# ArtNet_DMX_Controller.net
KiCad netlist of a schematic drawn in EAGLE
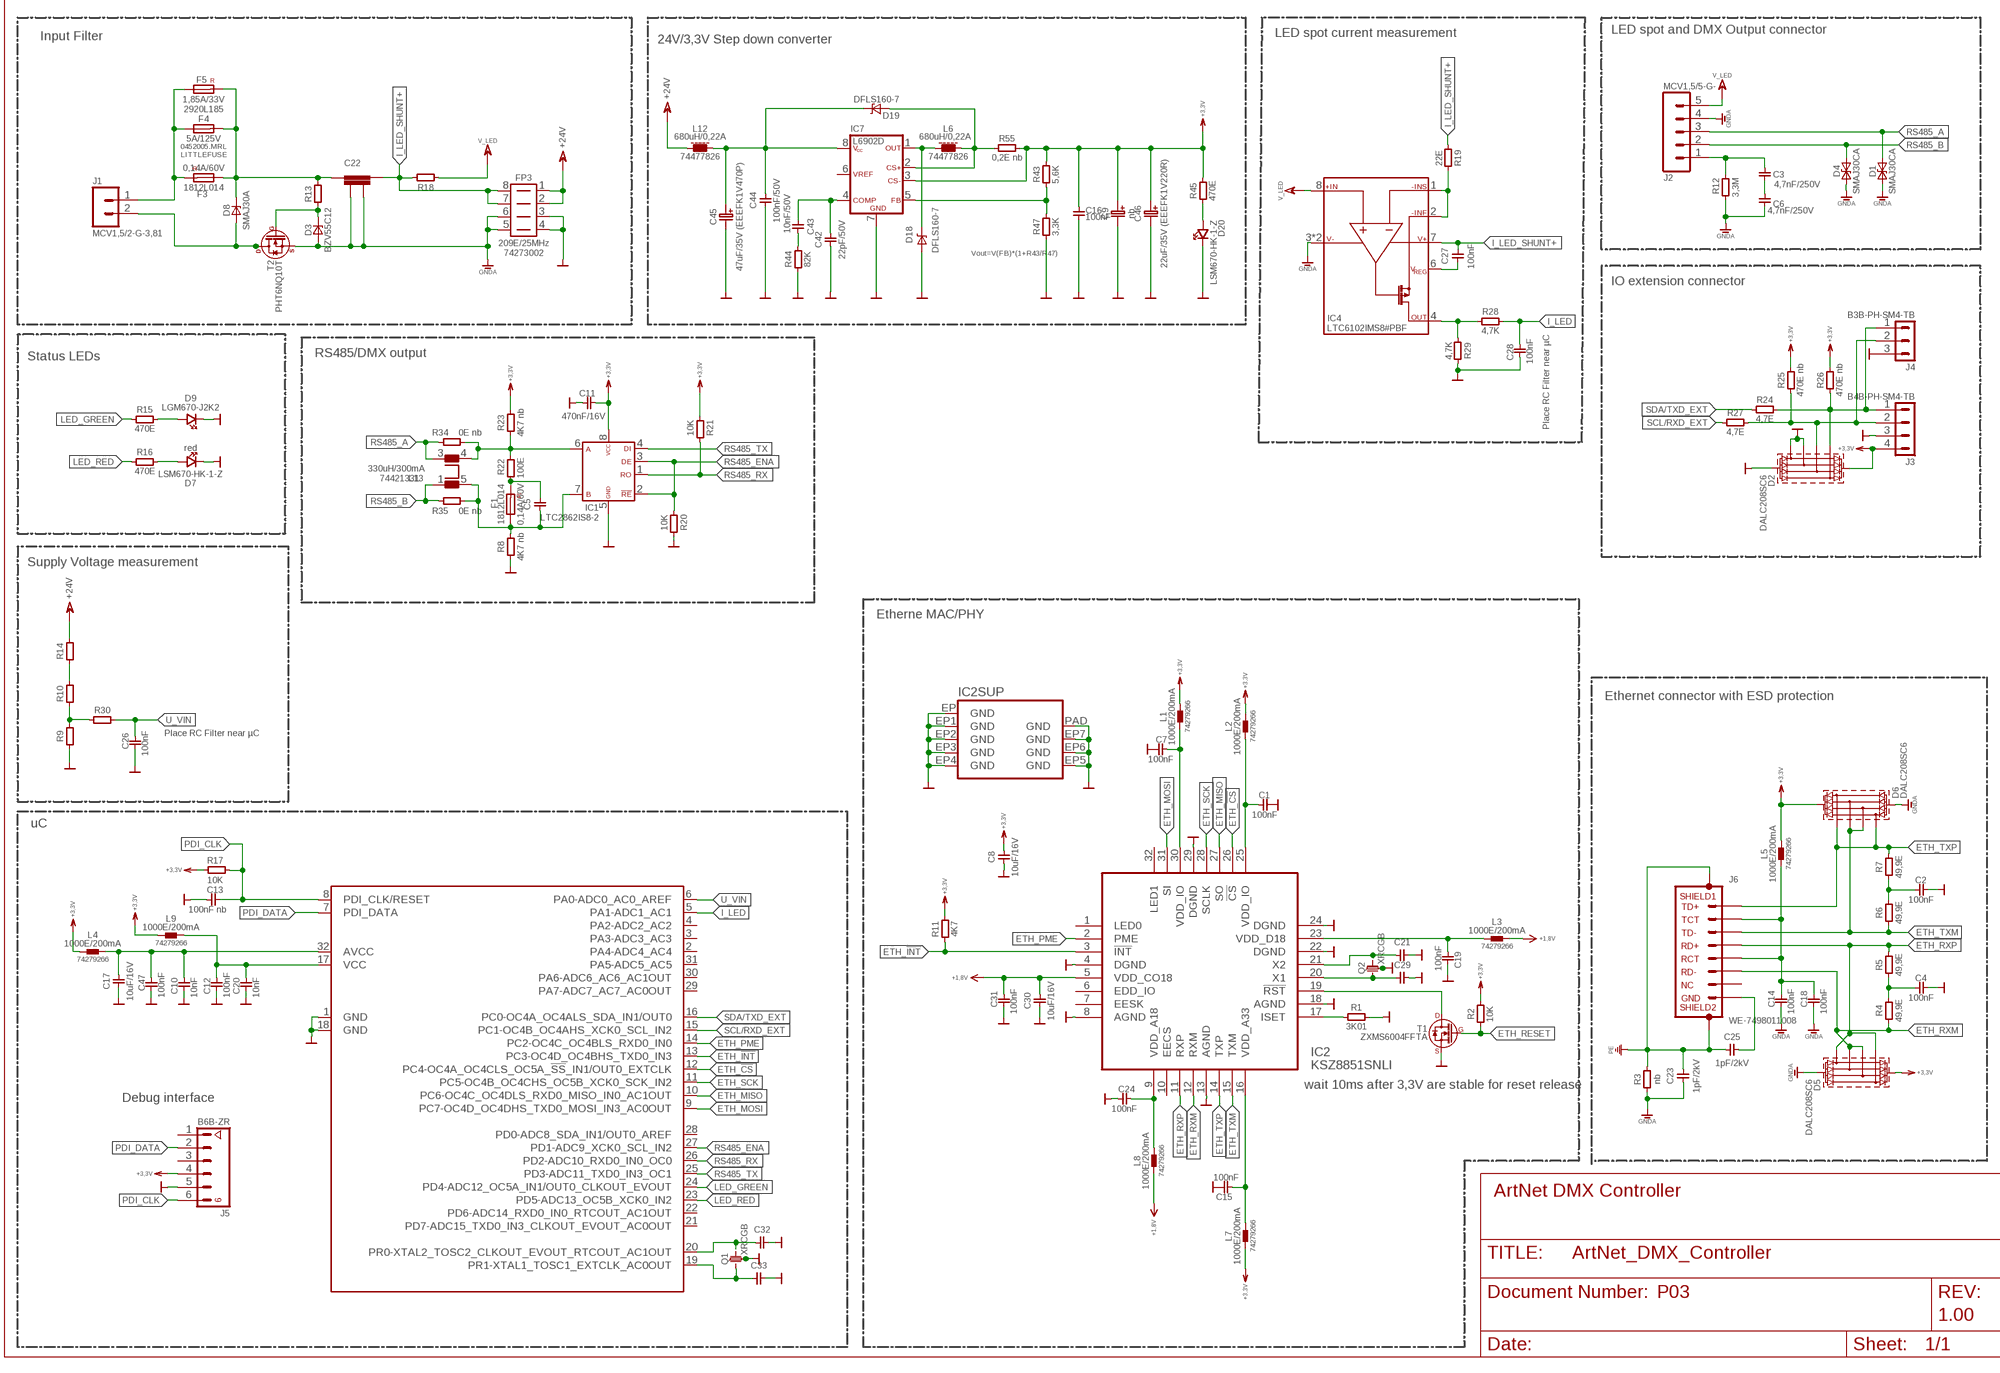
[diagram p0: schematic, sheet 1, part 1 of 2]
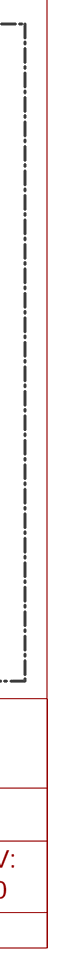
[diagram p1: schematic, sheet 1, part 2 of 2]

(export (version "E")
  (design (tool "Eeschema 10.0.6"))
  (components
    (comp (ref "C1")
      (value "100nF")
      (footprint "eagle-import:0603")
      (libsource (lib "eagle-import") (part "C-0603"))
    )
    (comp (ref "C2")
      (value "100nF")
      (footprint "eagle-import:0603")
      (libsource (lib "eagle-import") (part "C-0603"))
    )
    (comp (ref "C3")
      (value "4,7nF/250V")
      (footprint "eagle-import:2220")
      (libsource (lib "eagle-import") (part "C-2220"))
    )
    (comp (ref "C4")
      (value "100nF")
      (footprint "eagle-import:0603")
      (libsource (lib "eagle-import") (part "C-0603"))
    )
    (comp (ref "C5")
      (value "C-0805")
      (footprint "eagle-import:0805")
      (libsource (lib "eagle-import") (part "C-0805"))
    )
    (comp (ref "C6")
      (value "4,7nF/250V")
      (footprint "eagle-import:2220")
      (libsource (lib "eagle-import") (part "C-2220"))
    )
    (comp (ref "C7")
      (value "100nF")
      (footprint "eagle-import:0603")
      (libsource (lib "eagle-import") (part "C-0603"))
    )
    (comp (ref "C8")
      (value "10uF/16V")
      (footprint "eagle-import:0805")
      (libsource (lib "eagle-import") (part "C-0805"))
    )
    (comp (ref "C9")
      (value "nb")
      (footprint "eagle-import:6032")
      (libsource (lib "eagle-import") (part "TANTAL-6032"))
    )
    (comp (ref "C10")
      (value "10nF")
      (footprint "eagle-import:0603")
      (libsource (lib "eagle-import") (part "C-0603"))
    )
    (comp (ref "C11")
      (value "470nF/16V")
      (footprint "eagle-import:0603")
      (libsource (lib "eagle-import") (part "C-0603"))
    )
    (comp (ref "C12")
      (value "100nF")
      (footprint "eagle-import:0603")
      (libsource (lib "eagle-import") (part "C-0603"))
    )
    (comp (ref "C13")
      (value "100nF nb")
      (footprint "eagle-import:0603")
      (libsource (lib "eagle-import") (part "C-0603"))
    )
    (comp (ref "C14")
      (value "100nF")
      (footprint "eagle-import:0603")
      (libsource (lib "eagle-import") (part "C-0603"))
    )
    (comp (ref "C15")
      (value "100nF")
      (footprint "eagle-import:0603")
      (libsource (lib "eagle-import") (part "C-0603"))
    )
    (comp (ref "C16")
      (value "100nF")
      (footprint "eagle-import:0603")
      (libsource (lib "eagle-import") (part "C-0603"))
    )
    (comp (ref "C17")
      (value "10uF/16V")
      (footprint "eagle-import:0805")
      (libsource (lib "eagle-import") (part "C-0805"))
    )
    (comp (ref "C18")
      (value "100nF")
      (footprint "eagle-import:0603")
      (libsource (lib "eagle-import") (part "C-0603"))
    )
    (comp (ref "C19")
      (value "100nF")
      (footprint "eagle-import:0603")
      (libsource (lib "eagle-import") (part "C-0603"))
    )
    (comp (ref "C20")
      (value "10nF")
      (footprint "eagle-import:0603")
      (libsource (lib "eagle-import") (part "C-0603"))
    )
    (comp (ref "C21")
      (value "C-0603")
      (footprint "eagle-import:0603")
      (libsource (lib "eagle-import") (part "C-0603"))
    )
    (comp (ref "C22")
      (value "NFM55P")
      (footprint "eagle-import:NFM55P")
      (libsource (lib "eagle-import") (part "NFM?55P"))
    )
    (comp (ref "C23")
      (value "1pF/2kV")
      (footprint "eagle-import:1206")
      (libsource (lib "eagle-import") (part "C-1206"))
    )
    (comp (ref "C24")
      (value "100nF")
      (footprint "eagle-import:0603")
      (libsource (lib "eagle-import") (part "C-0603"))
    )
    (comp (ref "C25")
      (value "1pF/2kV")
      (footprint "eagle-import:1206")
      (libsource (lib "eagle-import") (part "C-1206"))
    )
    (comp (ref "C26")
      (value "100nF")
      (footprint "eagle-import:0603")
      (libsource (lib "eagle-import") (part "C-0603"))
    )
    (comp (ref "C27")
      (value "100nF")
      (footprint "eagle-import:0805")
      (libsource (lib "eagle-import") (part "C-0805"))
    )
    (comp (ref "C28")
      (value "100nF")
      (footprint "eagle-import:0603")
      (libsource (lib "eagle-import") (part "C-0603"))
    )
    (comp (ref "C29")
      (value "C-0603")
      (footprint "eagle-import:0603")
      (libsource (lib "eagle-import") (part "C-0603"))
    )
    (comp (ref "C30")
      (value "10uF/16V")
      (footprint "eagle-import:0805")
      (libsource (lib "eagle-import") (part "C-0805"))
    )
    (comp (ref "C31")
      (value "100nF")
      (footprint "eagle-import:0603")
      (libsource (lib "eagle-import") (part "C-0603"))
    )
    (comp (ref "C32")
      (value "C-0603")
      (footprint "eagle-import:0603")
      (libsource (lib "eagle-import") (part "C-0603"))
    )
    (comp (ref "C33")
      (value "C-0603")
      (footprint "eagle-import:0603")
      (libsource (lib "eagle-import") (part "C-0603"))
    )
    (comp (ref "C42")
      (value "22pF/50V")
      (footprint "eagle-import:0603")
      (libsource (lib "eagle-import") (part "C-0603"))
    )
    (comp (ref "C43")
      (value "10nF/50V")
      (footprint "eagle-import:0603")
      (libsource (lib "eagle-import") (part "C-0603"))
    )
    (comp (ref "C44")
      (value "100nF/50V")
      (footprint "eagle-import:0805")
      (libsource (lib "eagle-import") (part "C-0805"))
    )
    (comp (ref "C45")
      (value "47uF/35V (EEEFK1V470P)")
      (footprint "eagle-import:PANASONIC-SIZE-CODE-D")
      (libsource (lib "eagle-import") (part "ELKO-PANSIZE-D"))
    )
    (comp (ref "C46")
      (value "22uF/35V (EEEFK1V220R)")
      (footprint "eagle-import:PANASONIC-SIZE-CODE-D")
      (libsource (lib "eagle-import") (part "ELKO-PANSIZE-D"))
    )
    (comp (ref "C47")
      (value "100nF")
      (footprint "eagle-import:0603")
      (libsource (lib "eagle-import") (part "C-0603"))
    )
    (comp (ref "D1")
      (value "SMAJ30CA")
      (footprint "eagle-import:DO-214AC")
      (libsource (lib "eagle-import") (part "SMAJCA30"))
    )
    (comp (ref "D2")
      (value "DALC208SC6")
      (footprint "eagle-import:SOT23-6L")
      (libsource (lib "eagle-import") (part "DALC208SC6"))
    )
    (comp (ref "D3")
      (value "BZV55C12")
      (footprint "eagle-import:SOD80C")
      (libsource (lib "eagle-import") (part "BZ?55CV12"))
    )
    (comp (ref "D4")
      (value "SMAJ30CA")
      (footprint "eagle-import:DO-214AC")
      (libsource (lib "eagle-import") (part "SMAJCA30"))
    )
    (comp (ref "D5")
      (value "DALC208SC6")
      (footprint "eagle-import:SOT23-6L")
      (libsource (lib "eagle-import") (part "DALC208SC6"))
    )
    (comp (ref "D6")
      (value "DALC208SC6")
      (footprint "eagle-import:SOT23-6L")
      (libsource (lib "eagle-import") (part "DALC208SC6"))
    )
    (comp (ref "D7")
      (value "LSM670-HK-1-Z")
      (footprint "eagle-import:M670")
      (fields (field (name "COLOR") "red"))
      (libsource (lib "eagle-import") (part "L?M670S-HK-1-Z"))
    )
    (comp (ref "D8")
      (value "SMAJ30A")
      (footprint "eagle-import:DO-214AC")
      (libsource (lib "eagle-import") (part "SMAJA30"))
    )
    (comp (ref "D9")
      (value "LGM670-J2K2")
      (footprint "eagle-import:M670")
      (libsource (lib "eagle-import") (part "L?M670G-J2K2"))
    )
    (comp (ref "D18")
      (value "DFLS160-7")
      (footprint "eagle-import:POWERDI123")
      (libsource (lib "eagle-import") (part "DFLS160-7"))
    )
    (comp (ref "D19")
      (value "DFLS160-7")
      (footprint "eagle-import:POWERDI123")
      (libsource (lib "eagle-import") (part "DFLS160-7"))
    )
    (comp (ref "D20")
      (value "LSM670-HK-1-Z")
      (footprint "eagle-import:M670")
      (libsource (lib "eagle-import") (part "L?M670S-HK-1-Z"))
    )
    (comp (ref "F1")
      (value "0,14A/60V")
      (footprint "eagle-import:1812L")
      (fields (field (name "MPN") "1812L014"))
      (libsource (lib "eagle-import") (part "1812L014"))
    )
    (comp (ref "F3")
      (value "0,14A/60V")
      (footprint "eagle-import:1812L")
      (fields (field (name "MPN") "1812L014"))
      (libsource (lib "eagle-import") (part "1812L014"))
    )
    (comp (ref "F4")
      (value "5A/125V")
      (footprint "eagle-import:6.1X2.69MM")
      (fields (field (name "MF") "LITTLEFUSE") (field (name "MPN") "0452005.MRL"))
      (libsource (lib "eagle-import") (part "0452MRL005."))
    )
    (comp (ref "F5")
      (value "1,85A/33V")
      (footprint "eagle-import:2920L")
      (fields (field (name "MPN") "2920L185"))
      (libsource (lib "eagle-import") (part "2920L185"))
    )
    (comp (ref "FP3")
      (value "209E/25MHz")
      (footprint "eagle-import:WE-MLS-10,88MMX5,49MM")
      (fields (field (name "MPN") "74273002"))
      (libsource (lib "eagle-import") (part "WE-MLS-10,88MMX5,49MM-209E/25MHZ"))
    )
    (comp (ref "IC1")
      (value "LTC2862IS8-2")
      (footprint "eagle-import:SO8")
      (fields (field (name "MPN") "LTC2862IS8-2#TRPBF"))
      (libsource (lib "eagle-import") (part "LTC2862?-2S8I"))
    )
    (comp (ref "IC2")
      (value "KSZ8851SNLI")
      (footprint "eagle-import:QFN32_5X5")
      (libsource (lib "eagle-import") (part "IC_KSZ8851SNL"))
    )
    (comp (ref "IC3")
      (value "E5-TQFP")
      (footprint "eagle-import:TQFP32")
      (libsource (lib "eagle-import") (part "E5-TQFP"))
    )
    (comp (ref "IC4")
      (value "LTC6102IMS8#PBF")
      (footprint "eagle-import:MS8")
      (libsource (lib "eagle-import") (part "LTC6102?#PBFMS8I"))
    )
    (comp (ref "IC7")
      (value "L6902D")
      (footprint "eagle-import:SO8")
      (libsource (lib "eagle-import") (part "L6902D"))
    )
    (comp (ref "J1")
      (value "MCV1,5/2-G-3,81")
      (footprint "eagle-import:MCV1,5_2-G-3,81")
      (libsource (lib "eagle-import") (part "MCV1,5/2-G-3,81"))
    )
    (comp (ref "J2")
      (value "MCV1,5/5-G-")
      (footprint "eagle-import:MCV1,5_5-G-3,81_MOD")
      (libsource (lib "eagle-import") (part "MCV1,5/5-G-?"))
    )
    (comp (ref "J3")
      (value "B4B-PH-SM4-TB")
      (footprint "eagle-import:B4B-PH-SM4-TB")
      (libsource (lib "eagle-import") (part "?4B-PH-SM4-TBB"))
    )
    (comp (ref "J4")
      (value "B3B-PH-SM4-TB")
      (footprint "eagle-import:B3B-PH-SM4-TB")
      (libsource (lib "eagle-import") (part "?3B-PH-SM4-TBB"))
    )
    (comp (ref "J5")
      (value "B6B-ZR")
      (footprint "eagle-import:B6B-ZR")
      (libsource (lib "eagle-import") (part "?6B-ZRB"))
    )
    (comp (ref "J6")
      (value "WE-7498011008")
      (footprint "eagle-import:WE-749801108")
      (libsource (lib "eagle-import") (part "WE-7498011008"))
    )
    (comp (ref "L1")
      (value "1000E/200mA")
      (footprint "eagle-import:0603")
      (fields (field (name "MPN") "74279266"))
      (libsource (lib "eagle-import") (part "WE-CBF-0603-1000E/200MA"))
    )
    (comp (ref "L2")
      (value "1000E/200mA")
      (footprint "eagle-import:0603")
      (fields (field (name "MPN") "74279266"))
      (libsource (lib "eagle-import") (part "WE-CBF-0603-1000E/200MA"))
    )
    (comp (ref "L3")
      (value "1000E/200mA")
      (footprint "eagle-import:0603")
      (fields (field (name "MPN") "74279266"))
      (libsource (lib "eagle-import") (part "WE-CBF-0603-1000E/200MA"))
    )
    (comp (ref "L4")
      (value "1000E/200mA")
      (footprint "eagle-import:0603")
      (fields (field (name "MPN") "74279266"))
      (libsource (lib "eagle-import") (part "WE-CBF-0603-1000E/200MA"))
    )
    (comp (ref "L5")
      (value "1000E/200mA")
      (footprint "eagle-import:0603")
      (fields (field (name "MPN") "74279266"))
      (libsource (lib "eagle-import") (part "WE-CBF-0603-1000E/200MA"))
    )
    (comp (ref "L6")
      (value "680uH/0,22A")
      (footprint "eagle-import:73XX")
      (fields (field (name "MPN") "74477826"))
      (libsource (lib "eagle-import") (part "WE-PD-7332-680UH/0,22A"))
    )
    (comp (ref "L7")
      (value "1000E/200mA")
      (footprint "eagle-import:0603")
      (fields (field (name "MPN") "74279266"))
      (libsource (lib "eagle-import") (part "WE-CBF-0603-1000E/200MA"))
    )
    (comp (ref "L8")
      (value "1000E/200mA")
      (footprint "eagle-import:0603")
      (fields (field (name "MPN") "74279266"))
      (libsource (lib "eagle-import") (part "WE-CBF-0603-1000E/200MA"))
    )
    (comp (ref "L9")
      (value "1000E/200mA")
      (footprint "eagle-import:0603")
      (fields (field (name "MPN") "74279266"))
      (libsource (lib "eagle-import") (part "WE-CBF-0603-1000E/200MA"))
    )
    (comp (ref "L12")
      (value "680uH/0,22A")
      (footprint "eagle-import:73XX")
      (fields (field (name "MPN") "74477826"))
      (libsource (lib "eagle-import") (part "WE-PD-7332-680UH/0,22A"))
    )
    (comp (ref "L13")
      (value "330uH/300mA")
      (footprint "eagle-import:WE-SL1")
      (fields (field (name "MPN") "74421331"))
      (libsource (lib "eagle-import") (part "WE-SL1-330UH/300MA"))
    )
    (comp (ref "Q1")
      (value "XRCGB")
      (footprint "eagle-import:XRCGB")
      (libsource (lib "eagle-import") (part "XRCGB"))
    )
    (comp (ref "Q2")
      (value "XRCGB")
      (footprint "eagle-import:XRCGB")
      (libsource (lib "eagle-import") (part "XRCGB"))
    )
    (comp (ref "R1")
      (value "3K01")
      (footprint "eagle-import:0603")
      (libsource (lib "eagle-import") (part "R-0603"))
    )
    (comp (ref "R2")
      (value "10K")
      (footprint "eagle-import:0603")
      (libsource (lib "eagle-import") (part "R-0603"))
    )
    (comp (ref "R3")
      (value "nb")
      (footprint "eagle-import:1206")
      (libsource (lib "eagle-import") (part "R-1206"))
    )
    (comp (ref "R4")
      (value "49,9E")
      (footprint "eagle-import:0603")
      (libsource (lib "eagle-import") (part "R-0603"))
    )
    (comp (ref "R5")
      (value "49,9E")
      (footprint "eagle-import:0603")
      (libsource (lib "eagle-import") (part "R-0603"))
    )
    (comp (ref "R6")
      (value "49,9E")
      (footprint "eagle-import:0603")
      (libsource (lib "eagle-import") (part "R-0603"))
    )
    (comp (ref "R7")
      (value "49,9E")
      (footprint "eagle-import:0603")
      (libsource (lib "eagle-import") (part "R-0603"))
    )
    (comp (ref "R8")
      (value "4K7 nb")
      (footprint "eagle-import:0805")
      (libsource (lib "eagle-import") (part "R-0805"))
    )
    (comp (ref "R9")
      (value "R-0603")
      (footprint "eagle-import:0603")
      (libsource (lib "eagle-import") (part "R-0603"))
    )
    (comp (ref "R10")
      (value "R-0603")
      (footprint "eagle-import:0603")
      (libsource (lib "eagle-import") (part "R-0603"))
    )
    (comp (ref "R11")
      (value "4K7")
      (footprint "eagle-import:0603")
      (libsource (lib "eagle-import") (part "R-0603"))
    )
    (comp (ref "R12")
      (value "3,3M")
      (footprint "eagle-import:0207")
      (libsource (lib "eagle-import") (part "R-0207"))
    )
    (comp (ref "R13")
      (value "R-0805")
      (footprint "eagle-import:0805")
      (libsource (lib "eagle-import") (part "R-0805"))
    )
    (comp (ref "R14")
      (value "R-0603")
      (footprint "eagle-import:0603")
      (libsource (lib "eagle-import") (part "R-0603"))
    )
    (comp (ref "R15")
      (value "470E")
      (footprint "eagle-import:0603")
      (libsource (lib "eagle-import") (part "R-0603"))
    )
    (comp (ref "R16")
      (value "470E")
      (footprint "eagle-import:0603")
      (libsource (lib "eagle-import") (part "R-0603"))
    )
    (comp (ref "R17")
      (value "10K")
      (footprint "eagle-import:0603")
      (libsource (lib "eagle-import") (part "R-0603"))
    )
    (comp (ref "R18")
      (value "R-2512")
      (footprint "eagle-import:2512")
      (libsource (lib "eagle-import") (part "R-2512"))
    )
    (comp (ref "R19")
      (value "22E")
      (footprint "eagle-import:0603")
      (libsource (lib "eagle-import") (part "R-0603"))
    )
    (comp (ref "R20")
      (value "10K")
      (footprint "eagle-import:0603")
      (libsource (lib "eagle-import") (part "R-0603"))
    )
    (comp (ref "R21")
      (value "10K")
      (footprint "eagle-import:0603")
      (libsource (lib "eagle-import") (part "R-0603"))
    )
    (comp (ref "R22")
      (value "100E")
      (footprint "eagle-import:0207")
      (libsource (lib "eagle-import") (part "R-0207"))
    )
    (comp (ref "R23")
      (value "4K7 nb")
      (footprint "eagle-import:0805")
      (libsource (lib "eagle-import") (part "R-0805"))
    )
    (comp (ref "R24")
      (value "4,7E")
      (footprint "eagle-import:0603")
      (libsource (lib "eagle-import") (part "R-0603"))
    )
    (comp (ref "R25")
      (value "470E nb")
      (footprint "eagle-import:0603")
      (libsource (lib "eagle-import") (part "R-0603"))
    )
    (comp (ref "R26")
      (value "470E nb")
      (footprint "eagle-import:0603")
      (libsource (lib "eagle-import") (part "R-0603"))
    )
    (comp (ref "R27")
      (value "4,7E")
      (footprint "eagle-import:0603")
      (libsource (lib "eagle-import") (part "R-0603"))
    )
    (comp (ref "R28")
      (value "4,7K")
      (footprint "eagle-import:0603")
      (libsource (lib "eagle-import") (part "R-0603"))
    )
    (comp (ref "R29")
      (value "4,7K")
      (footprint "eagle-import:0603")
      (libsource (lib "eagle-import") (part "R-0603"))
    )
    (comp (ref "R30")
      (value "R-0603")
      (footprint "eagle-import:0603")
      (libsource (lib "eagle-import") (part "R-0603"))
    )
    (comp (ref "R34")
      (value "0E nb")
      (footprint "eagle-import:0805")
      (libsource (lib "eagle-import") (part "R-0805"))
    )
    (comp (ref "R35")
      (value "0E nb")
      (footprint "eagle-import:0805")
      (libsource (lib "eagle-import") (part "R-0805"))
    )
    (comp (ref "R43")
      (value "5,6K")
      (footprint "eagle-import:0603")
      (libsource (lib "eagle-import") (part "R-0603"))
    )
    (comp (ref "R44")
      (value "82K")
      (footprint "eagle-import:0603")
      (libsource (lib "eagle-import") (part "R-0603"))
    )
    (comp (ref "R45")
      (value "470E")
      (footprint "eagle-import:0603")
      (libsource (lib "eagle-import") (part "R-0603"))
    )
    (comp (ref "R47")
      (value "3,3K")
      (footprint "eagle-import:0603")
      (libsource (lib "eagle-import") (part "R-0603"))
    )
    (comp (ref "R55")
      (value "0,2E nb")
      (footprint "eagle-import:0805")
      (libsource (lib "eagle-import") (part "R-0805"))
    )
    (comp (ref "T1")
      (value "ZXMS6004FFTA")
      (footprint "eagle-import:SOT-23")
      (libsource (lib "eagle-import") (part "ZXMS6004?TAFF"))
    )
    (comp (ref "T2")
      (value "PHT6NQ10T")
      (footprint "eagle-import:SOT223")
      (libsource (lib "eagle-import") (part "PHT6NQ10T"))
    )
  )
  (nets
    (net (code "1") (name "+1,8V") (class "Default")
      (node (ref "C30") (pin "2") (pinfunction "2_2") (pintype "passive"))
      (node (ref "C31") (pin "2") (pinfunction "2_2") (pintype "passive"))
      (node (ref "IC2") (pin "5") (pinfunction "VDD_CO18_5") (pintype "bidirectional"))
      (node (ref "L3") (pin "2") (pinfunction "2_2") (pintype "passive"))
      (node (ref "L8") (pin "1") (pinfunction "1_1") (pintype "passive"))
    )
    (net (code "2") (name "+3,3V") (class "Default")
      (node (ref "C11") (pin "2") (pinfunction "2_2") (pintype "passive"))
      (node (ref "C16") (pin "2") (pinfunction "2_2") (pintype "passive"))
      (node (ref "C46") (pin "+") (pinfunction "+_+") (pintype "passive"))
      (node (ref "C8") (pin "1") (pinfunction "1_1") (pintype "passive"))
      (node (ref "C9") (pin "PLUS") (pinfunction "+_PLUS") (pintype "passive"))
      (node (ref "D2") (pin "2") (pinfunction "REF2_2") (pintype "passive"))
      (node (ref "D5") (pin "2") (pinfunction "REF2_2") (pintype "passive"))
      (node (ref "D6") (pin "2") (pinfunction "REF2_2") (pintype "passive"))
      (node (ref "IC1") (pin "8") (pinfunction "VCC_8") (pintype "power_in"))
      (node (ref "IC7") (pin "3") (pinfunction "CS-_3") (pintype "input"))
      (node (ref "J3") (pin "4") (pinfunction "4_4") (pintype "passive"))
      (node (ref "J5") (pin "4") (pinfunction "4_4") (pintype "passive"))
      (node (ref "L1") (pin "2") (pinfunction "2_2") (pintype "passive"))
      (node (ref "L2") (pin "2") (pinfunction "2_2") (pintype "passive"))
      (node (ref "L4") (pin "1") (pinfunction "1_1") (pintype "passive"))
      (node (ref "L5") (pin "2") (pinfunction "2_2") (pintype "passive"))
      (node (ref "L7") (pin "1") (pinfunction "1_1") (pintype "passive"))
      (node (ref "L9") (pin "1") (pinfunction "1_1") (pintype "passive"))
      (node (ref "R11") (pin "2") (pinfunction "2_2") (pintype "passive"))
      (node (ref "R17") (pin "2") (pinfunction "2_2") (pintype "passive"))
      (node (ref "R2") (pin "2") (pinfunction "2_2") (pintype "passive"))
      (node (ref "R21") (pin "2") (pinfunction "2_2") (pintype "passive"))
      (node (ref "R23") (pin "2") (pinfunction "2_2") (pintype "passive"))
      (node (ref "R25") (pin "2") (pinfunction "2_2") (pintype "passive"))
      (node (ref "R26") (pin "2") (pinfunction "2_2") (pintype "passive"))
      (node (ref "R43") (pin "2") (pinfunction "2_2") (pintype "passive"))
      (node (ref "R45") (pin "2") (pinfunction "2_2") (pintype "passive"))
      (node (ref "R55") (pin "2") (pinfunction "2_2") (pintype "passive"))
    )
    (net (code "3") (name "+24V") (class "Default")
      (node (ref "FP3") (pin "1") (pinfunction "1_1") (pintype "passive"))
      (node (ref "FP3") (pin "2") (pinfunction "2_2") (pintype "passive"))
      (node (ref "L12") (pin "1") (pinfunction "1_1") (pintype "passive"))
      (node (ref "R14") (pin "2") (pinfunction "2_2") (pintype "passive"))
    )
    (net (code "4") (name "/ETH_~{CS}") (class "Default")
      (node (ref "IC2") (pin "26") (pinfunction "~{CS}_26") (pintype "bidirectional"))
      (node (ref "IC3") (pin "12") (pinfunction "PC4-OC4A_OC4CLS_OC5A_~{SS}_IN1/OUT0_EXTCLK_12") (pintype "bidirectional"))
    )
    (net (code "5") (name "/ETH_~{INT}") (class "Default")
      (node (ref "IC2") (pin "3") (pinfunction "~{INT}_3") (pintype "bidirectional"))
      (node (ref "IC3") (pin "13") (pinfunction "PC3-OC4D_OC4BHS_TXD0_IN3_13") (pintype "bidirectional"))
      (node (ref "R11") (pin "1") (pinfunction "1_1") (pintype "passive"))
    )
    (net (code "6") (name "ETH_MISO") (class "Default")
      (node (ref "IC2") (pin "27") (pinfunction "SO_27") (pintype "bidirectional"))
      (node (ref "IC3") (pin "10") (pinfunction "PC6-OC4C_OC4DLS_RXD0_MISO_IN0_AC1OUT_10") (pintype "bidirectional"))
    )
    (net (code "7") (name "ETH_MOSI") (class "Default")
      (node (ref "IC2") (pin "31") (pinfunction "SI_31") (pintype "bidirectional"))
      (node (ref "IC3") (pin "9") (pinfunction "PC7-OC4D_OC4DHS_TXD0_MOSI_IN3_AC0OUT_9") (pintype "bidirectional"))
    )
    (net (code "8") (name "ETH_PME") (class "Default")
      (node (ref "IC2") (pin "2") (pinfunction "PME_2") (pintype "bidirectional"))
      (node (ref "IC3") (pin "14") (pinfunction "PC2-OC4C_OC4BLS_RXD0_IN0_14") (pintype "bidirectional"))
    )
    (net (code "9") (name "ETH_RESET") (class "Default")
      (node (ref "R2") (pin "1") (pinfunction "1_1") (pintype "passive"))
      (node (ref "T1") (pin "1") (pinfunction "G_1") (pintype "passive"))
    )
    (net (code "10") (name "ETH_RXM") (class "Default")
      (node (ref "D5") (pin "3") (pinfunction "I/O2_3") (pintype "passive"))
      (node (ref "D5") (pin "4") (pinfunction "I/O3_4") (pintype "passive"))
      (node (ref "IC2") (pin "12") (pinfunction "RXM_12") (pintype "bidirectional"))
      (node (ref "J6") (pin "P$6") (pinfunction "RD-_P$6") (pintype "passive"))
      (node (ref "R4") (pin "1") (pinfunction "1_1") (pintype "passive"))
    )
    (net (code "11") (name "ETH_RXP") (class "Default")
      (node (ref "D5") (pin "1") (pinfunction "I/O1_1") (pintype "passive"))
      (node (ref "D5") (pin "6") (pinfunction "I/O4_6") (pintype "passive"))
      (node (ref "IC2") (pin "11") (pinfunction "RXP_11") (pintype "bidirectional"))
      (node (ref "J6") (pin "P$3") (pinfunction "RD+_P$3") (pintype "passive"))
      (node (ref "R5") (pin "2") (pinfunction "2_2") (pintype "passive"))
    )
    (net (code "12") (name "ETH_SCK") (class "Default")
      (node (ref "IC2") (pin "28") (pinfunction "SCLK_28") (pintype "bidirectional"))
      (node (ref "IC3") (pin "11") (pinfunction "PC5-OC4B_OC4CHS_OC5B_XCK0_SCK_IN2_11") (pintype "bidirectional"))
    )
    (net (code "13") (name "ETH_TXM") (class "Default")
      (node (ref "D6") (pin "3") (pinfunction "I/O2_3") (pintype "passive"))
      (node (ref "D6") (pin "4") (pinfunction "I/O3_4") (pintype "passive"))
      (node (ref "IC2") (pin "15") (pinfunction "TXM_15") (pintype "bidirectional"))
      (node (ref "J6") (pin "P$2") (pinfunction "TD-_P$2") (pintype "passive"))
      (node (ref "R6") (pin "1") (pinfunction "1_1") (pintype "passive"))
    )
    (net (code "14") (name "ETH_TXP") (class "Default")
      (node (ref "D6") (pin "1") (pinfunction "I/O1_1") (pintype "passive"))
      (node (ref "D6") (pin "6") (pinfunction "I/O4_6") (pintype "passive"))
      (node (ref "IC2") (pin "14") (pinfunction "TXP_14") (pintype "bidirectional"))
      (node (ref "J6") (pin "P$1") (pinfunction "TD+_P$1") (pintype "passive"))
      (node (ref "R7") (pin "2") (pinfunction "2_2") (pintype "passive"))
    )
    (net (code "15") (name "GND") (class "Default")
      (node (ref "C1") (pin "2") (pinfunction "2_2") (pintype "passive"))
      (node (ref "C10") (pin "1") (pinfunction "1_1") (pintype "passive"))
      (node (ref "C11") (pin "1") (pinfunction "1_1") (pintype "passive"))
      (node (ref "C12") (pin "1") (pinfunction "1_1") (pintype "passive"))
      (node (ref "C13") (pin "2") (pinfunction "2_2") (pintype "passive"))
      (node (ref "C15") (pin "2") (pinfunction "2_2") (pintype "passive"))
      (node (ref "C16") (pin "1") (pinfunction "1_1") (pintype "passive"))
      (node (ref "C17") (pin "1") (pinfunction "1_1") (pintype "passive"))
      (node (ref "C19") (pin "2") (pinfunction "2_2") (pintype "passive"))
      (node (ref "C2") (pin "2") (pinfunction "2_2") (pintype "passive"))
      (node (ref "C20") (pin "1") (pinfunction "1_1") (pintype "passive"))
      (node (ref "C21") (pin "2") (pinfunction "2_2") (pintype "passive"))
      (node (ref "C24") (pin "1") (pinfunction "1_1") (pintype "passive"))
      (node (ref "C26") (pin "1") (pinfunction "1_1") (pintype "passive"))
      (node (ref "C28") (pin "1") (pinfunction "1_1") (pintype "passive"))
      (node (ref "C29") (pin "2") (pinfunction "2_2") (pintype "passive"))
      (node (ref "C30") (pin "1") (pinfunction "1_1") (pintype "passive"))
      (node (ref "C31") (pin "1") (pinfunction "1_1") (pintype "passive"))
      (node (ref "C32") (pin "2") (pinfunction "2_2") (pintype "passive"))
      (node (ref "C33") (pin "2") (pinfunction "2_2") (pintype "passive"))
      (node (ref "C4") (pin "2") (pinfunction "2_2") (pintype "passive"))
      (node (ref "C42") (pin "1") (pinfunction "1_1") (pintype "passive"))
      (node (ref "C44") (pin "1") (pinfunction "1_1") (pintype "passive"))
      (node (ref "C45") (pin "-") (pinfunction "-_-") (pintype "passive"))
      (node (ref "C46") (pin "-") (pinfunction "-_-") (pintype "passive"))
      (node (ref "C47") (pin "1") (pinfunction "1_1") (pintype "passive"))
      (node (ref "C7") (pin "2") (pinfunction "2_2") (pintype "passive"))
      (node (ref "C8") (pin "2") (pinfunction "2_2") (pintype "passive"))
      (node (ref "C9") (pin "MINUS") (pinfunction "-_MINUS") (pintype "passive"))
      (node (ref "D18") (pin "A") (pinfunction "A_A") (pintype "passive"))
      (node (ref "D2") (pin "1") (pinfunction "I/O1_1") (pintype "passive"))
      (node (ref "D2") (pin "3") (pinfunction "I/O2_3") (pintype "passive"))
      (node (ref "D2") (pin "5") (pinfunction "REF1_5") (pintype "passive"))
      (node (ref "D20") (pin "K") (pinfunction "K_K") (pintype "passive"))
      (node (ref "D7") (pin "K") (pinfunction "K_K") (pintype "passive"))
      (node (ref "D9") (pin "K") (pinfunction "K_K") (pintype "passive"))
      (node (ref "FP3") (pin "3") (pinfunction "3_3") (pintype "passive"))
      (node (ref "FP3") (pin "4") (pinfunction "4_4") (pintype "passive"))
      (node (ref "IC1") (pin "5") (pinfunction "GND_5") (pintype "power_in"))
      (node (ref "IC2") (pin "13") (pinfunction "AGND_13") (pintype "bidirectional"))
      (node (ref "IC2") (pin "18") (pinfunction "AGND_18") (pintype "power_in"))
      (node (ref "IC2") (pin "22") (pinfunction "DGND_22") (pintype "bidirectional"))
      (node (ref "IC2") (pin "24") (pinfunction "DGND_24") (pintype "bidirectional"))
      (node (ref "IC2") (pin "29") (pinfunction "DGND_29") (pintype "bidirectional"))
      (node (ref "IC2") (pin "4") (pinfunction "DGND_4") (pintype "power_in"))
      (node (ref "IC2") (pin "8") (pinfunction "AGND_8") (pintype "bidirectional"))
      (node (ref "IC2") (pin "EP") (pinfunction "GND_EP") (pintype "power_in"))
      (node (ref "IC2") (pin "EP1") (pinfunction "GND_EP1") (pintype "power_in"))
      (node (ref "IC2") (pin "EP2") (pinfunction "GND_EP2") (pintype "power_in"))
      (node (ref "IC2") (pin "EP3") (pinfunction "GND_EP3") (pintype "power_in"))
      (node (ref "IC2") (pin "EP4") (pinfunction "GND_EP4") (pintype "power_in"))
      (node (ref "IC2") (pin "EP5") (pinfunction "GND_EP5") (pintype "power_in"))
      (node (ref "IC2") (pin "EP6") (pinfunction "GND_EP6") (pintype "power_in"))
      (node (ref "IC2") (pin "EP7") (pinfunction "GND_EP7") (pintype "power_in"))
      (node (ref "IC2") (pin "PAD") (pinfunction "GND_PAD") (pintype "power_in"))
      (node (ref "IC3") (pin "1") (pinfunction "GND_1") (pintype "power_in"))
      (node (ref "IC3") (pin "18") (pinfunction "GND_18") (pintype "power_in"))
      (node (ref "IC7") (pin "7") (pinfunction "GND_7") (pintype "power_in"))
      (node (ref "J3") (pin "3") (pinfunction "3_3") (pintype "passive"))
      (node (ref "J4") (pin "3") (pinfunction "3_3") (pintype "passive"))
      (node (ref "J5") (pin "5") (pinfunction "5_5") (pintype "passive"))
      (node (ref "Q1") (pin "3") (pinfunction "P$3_3") (pintype "bidirectional"))
      (node (ref "Q1") (pin "4") (pinfunction "P$4_4") (pintype "bidirectional"))
      (node (ref "Q2") (pin "3") (pinfunction "P$3_3") (pintype "bidirectional"))
      (node (ref "Q2") (pin "4") (pinfunction "P$4_4") (pintype "bidirectional"))
      (node (ref "R1") (pin "2") (pinfunction "2_2") (pintype "passive"))
      (node (ref "R20") (pin "1") (pinfunction "1_1") (pintype "passive"))
      (node (ref "R29") (pin "2") (pinfunction "2_2") (pintype "passive"))
      (node (ref "R44") (pin "1") (pinfunction "1_1") (pintype "passive"))
      (node (ref "R47") (pin "1") (pinfunction "1_1") (pintype "passive"))
      (node (ref "R8") (pin "1") (pinfunction "1_1") (pintype "passive"))
      (node (ref "R9") (pin "1") (pinfunction "1_1") (pintype "passive"))
      (node (ref "T1") (pin "2") (pinfunction "S_2") (pintype "passive"))
    )
    (net (code "16") (name "GNDA") (class "Default")
      (node (ref "C14") (pin "1") (pinfunction "1_1") (pintype "passive"))
      (node (ref "C18") (pin "1") (pinfunction "1_1") (pintype "passive"))
      (node (ref "C22") (pin "3") (pinfunction "3_3") (pintype "passive"))
      (node (ref "C22") (pin "4") (pinfunction "4_4") (pintype "passive"))
      (node (ref "C23") (pin "1") (pinfunction "1_1") (pintype "passive"))
      (node (ref "C6") (pin "P$1") (pinfunction "1_P$1") (pintype "passive"))
      (node (ref "D1") (pin "K") (pinfunction "2_K") (pintype "passive"))
      (node (ref "D3") (pin "A") (pinfunction "A_A") (pintype "passive"))
      (node (ref "D4") (pin "K") (pinfunction "2_K") (pintype "passive"))
      (node (ref "D5") (pin "5") (pinfunction "REF1_5") (pintype "passive"))
      (node (ref "D6") (pin "5") (pinfunction "REF1_5") (pintype "passive"))
      (node (ref "FP3") (pin "5") (pinfunction "5_5") (pintype "passive"))
      (node (ref "FP3") (pin "6") (pinfunction "6_6") (pintype "passive"))
      (node (ref "IC4") (pin "3") (pinfunction "V-_3") (pintype "power_in"))
      (node (ref "IC4") (pin "5") (pinfunction "V-_5") (pintype "power_in"))
      (node (ref "J2") (pin "4") (pinfunction "4_4") (pintype "passive"))
      (node (ref "R12") (pin "1") (pinfunction "1_1") (pintype "passive"))
      (node (ref "R3") (pin "1") (pinfunction "1_1") (pintype "passive"))
      (node (ref "T2") (pin "3") (pinfunction "S_3") (pintype "passive"))
    )
    (net (code "17") (name "I_LED") (class "Default")
      (node (ref "C28") (pin "2") (pinfunction "2_2") (pintype "passive"))
      (node (ref "IC3") (pin "5") (pinfunction "PA1-ADC1_AC1_5") (pintype "bidirectional"))
      (node (ref "R28") (pin "2") (pinfunction "2_2") (pintype "passive"))
    )
    (net (code "18") (name "I_LED_SHUNT+") (class "Default")
      (node (ref "C22") (pin "2") (pinfunction "2_2") (pintype "passive"))
      (node (ref "C27") (pin "2") (pinfunction "2_2") (pintype "passive"))
      (node (ref "FP3") (pin "7") (pinfunction "7_7") (pintype "passive"))
      (node (ref "FP3") (pin "8") (pinfunction "8_8") (pintype "passive"))
      (node (ref "IC4") (pin "7") (pinfunction "V+_7") (pintype "power_in"))
      (node (ref "R18") (pin "2") (pinfunction "2_2") (pintype "passive"))
      (node (ref "R19") (pin "1") (pinfunction "1_1") (pintype "passive"))
    )
    (net (code "19") (name "LED_GREEN") (class "Default")
      (node (ref "IC3") (pin "24") (pinfunction "PD4-ADC12_OC5A_IN1/OUT0_CLKOUT_EVOUT_24") (pintype "bidirectional"))
      (node (ref "R15") (pin "1") (pinfunction "1_1") (pintype "passive"))
    )
    (net (code "20") (name "LED_RED") (class "Default")
      (node (ref "IC3") (pin "23") (pinfunction "PD5-ADC13_OC5B_XCK0_IN2_23") (pintype "bidirectional"))
      (node (ref "R16") (pin "1") (pinfunction "1_1") (pintype "passive"))
    )
    (net (code "21") (name "Net-(C1-Pad1)") (class "Default")
      (node (ref "C1") (pin "1") (pinfunction "1_1") (pintype "passive"))
      (node (ref "IC2") (pin "25") (pinfunction "VDD_IO_25") (pintype "bidirectional"))
      (node (ref "L2") (pin "1") (pinfunction "1_1") (pintype "passive"))
    )
    (net (code "22") (name "Net-(C2-Pad1)") (class "Default")
      (node (ref "C2") (pin "1") (pinfunction "1_1") (pintype "passive"))
      (node (ref "R6") (pin "2") (pinfunction "2_2") (pintype "passive"))
      (node (ref "R7") (pin "1") (pinfunction "1_1") (pintype "passive"))
    )
    (net (code "23") (name "Net-(C3-1)") (class "Default")
      (node (ref "C3") (pin "P$1") (pinfunction "1_P$1") (pintype "passive"))
      (node (ref "C6") (pin "P$2") (pinfunction "2_P$2") (pintype "passive"))
    )
    (net (code "24") (name "Net-(C3-2)") (class "Default")
      (node (ref "C3") (pin "P$2") (pinfunction "2_P$2") (pintype "passive"))
      (node (ref "J2") (pin "1") (pinfunction "1_1") (pintype "passive"))
      (node (ref "R12") (pin "2") (pinfunction "2_2") (pintype "passive"))
    )
    (net (code "25") (name "Net-(C4-Pad1)") (class "Default")
      (node (ref "C4") (pin "1") (pinfunction "1_1") (pintype "passive"))
      (node (ref "R4") (pin "2") (pinfunction "2_2") (pintype "passive"))
      (node (ref "R5") (pin "1") (pinfunction "1_1") (pintype "passive"))
    )
    (net (code "26") (name "Net-(C5-Pad2)") (class "Default")
      (node (ref "C5") (pin "2") (pinfunction "2_2") (pintype "passive"))
      (node (ref "F1") (pin "2") (pinfunction "2_2") (pintype "passive"))
      (node (ref "R22") (pin "1") (pinfunction "1_1") (pintype "passive"))
    )
    (net (code "27") (name "Net-(C7-Pad1)") (class "Default")
      (node (ref "C7") (pin "1") (pinfunction "1_1") (pintype "passive"))
      (node (ref "IC2") (pin "30") (pinfunction "VDD_IO_30") (pintype "bidirectional"))
      (node (ref "L1") (pin "1") (pinfunction "1_1") (pintype "passive"))
    )
    (net (code "28") (name "Net-(C22-Pad1)") (class "Default")
      (node (ref "C22") (pin "1") (pinfunction "1_1") (pintype "passive"))
      (node (ref "D8") (pin "K") (pinfunction "K_K") (pintype "passive"))
      (node (ref "F3") (pin "1") (pinfunction "1_1") (pintype "passive"))
      (node (ref "F4") (pin "2") (pinfunction "2_2") (pintype "passive"))
      (node (ref "F5") (pin "2") (pinfunction "2_2") (pintype "passive"))
      (node (ref "R13") (pin "2") (pinfunction "2_2") (pintype "passive"))
    )
    (net (code "29") (name "Net-(C43-Pad2)") (class "Default")
      (node (ref "C43") (pin "2") (pinfunction "2_2") (pintype "passive"))
      (node (ref "R44") (pin "2") (pinfunction "2_2") (pintype "passive"))
    )
    (net (code "30") (name "Net-(D2-I{slash}O3)") (class "Default")
      (node (ref "D2") (pin "4") (pinfunction "I/O3_4") (pintype "passive"))
      (node (ref "J3") (pin "2") (pinfunction "2_2") (pintype "passive"))
      (node (ref "J4") (pin "2") (pinfunction "2_2") (pintype "passive"))
      (node (ref "R25") (pin "1") (pinfunction "1_1") (pintype "passive"))
      (node (ref "R27") (pin "2") (pinfunction "2_2") (pintype "passive"))
    )
    (net (code "31") (name "Net-(D2-I{slash}O4)") (class "Default")
      (node (ref "D2") (pin "6") (pinfunction "I/O4_6") (pintype "passive"))
      (node (ref "J3") (pin "1") (pinfunction "1_1") (pintype "passive"))
      (node (ref "J4") (pin "1") (pinfunction "1_1") (pintype "passive"))
      (node (ref "R24") (pin "2") (pinfunction "2_2") (pintype "passive"))
      (node (ref "R26") (pin "1") (pinfunction "1_1") (pintype "passive"))
    )
    (net (code "32") (name "Net-(D7-PadA)") (class "Default")
      (node (ref "D7") (pin "A") (pinfunction "A_A") (pintype "passive"))
      (node (ref "R16") (pin "2") (pinfunction "2_2") (pintype "passive"))
    )
    (net (code "33") (name "Net-(D9-PadA)") (class "Default")
      (node (ref "D9") (pin "A") (pinfunction "A_A") (pintype "passive"))
      (node (ref "R15") (pin "2") (pinfunction "2_2") (pintype "passive"))
    )
    (net (code "34") (name "Net-(D20-PadA)") (class "Default")
      (node (ref "D20") (pin "A") (pinfunction "A_A") (pintype "passive"))
      (node (ref "R45") (pin "1") (pinfunction "1_1") (pintype "passive"))
    )
    (net (code "35") (name "Net-(F3-Pad2)") (class "Default")
      (node (ref "F3") (pin "2") (pinfunction "2_2") (pintype "passive"))
      (node (ref "F4") (pin "1") (pinfunction "1_1") (pintype "passive"))
      (node (ref "F5") (pin "1") (pinfunction "1_1") (pintype "passive"))
      (node (ref "J1") (pin "1") (pinfunction "1_1") (pintype "passive"))
    )
    (net (code "36") (name "Net-(IC1-A)") (class "Default")
      (node (ref "IC1") (pin "6") (pinfunction "A_6") (pintype "bidirectional"))
      (node (ref "L13") (pin "4") (pinfunction "3_4") (pintype "passive"))
      (node (ref "R22") (pin "2") (pinfunction "2_2") (pintype "passive"))
      (node (ref "R23") (pin "1") (pinfunction "1_1") (pintype "passive"))
      (node (ref "R34") (pin "2") (pinfunction "2_2") (pintype "passive"))
    )
    (net (code "37") (name "Net-(IC1-B)") (class "Default")
      (node (ref "C5") (pin "1") (pinfunction "1_1") (pintype "passive"))
      (node (ref "F1") (pin "1") (pinfunction "1_1") (pintype "passive"))
      (node (ref "IC1") (pin "7") (pinfunction "B_7") (pintype "bidirectional"))
      (node (ref "L13") (pin "5") (pinfunction "2_5") (pintype "passive"))
      (node (ref "R35") (pin "2") (pinfunction "2_2") (pintype "passive"))
      (node (ref "R8") (pin "2") (pinfunction "2_2") (pintype "passive"))
    )
    (net (code "38") (name "Net-(IC2A-ISET)") (class "Default")
      (node (ref "IC2") (pin "17") (pinfunction "ISET_17") (pintype "bidirectional"))
      (node (ref "R1") (pin "1") (pinfunction "1_1") (pintype "passive"))
    )
    (net (code "39") (name "Net-(IC2A-VDD_A18)") (class "Default")
      (node (ref "C24") (pin "2") (pinfunction "2_2") (pintype "passive"))
      (node (ref "IC2") (pin "9") (pinfunction "VDD_A18_9") (pintype "bidirectional"))
      (node (ref "L8") (pin "2") (pinfunction "2_2") (pintype "passive"))
    )
    (net (code "40") (name "Net-(IC2A-VDD_A33)") (class "Default")
      (node (ref "C15") (pin "1") (pinfunction "1_1") (pintype "passive"))
      (node (ref "IC2") (pin "16") (pinfunction "VDD_A33_16") (pintype "bidirectional"))
      (node (ref "L7") (pin "2") (pinfunction "2_2") (pintype "passive"))
    )
    (net (code "41") (name "Net-(IC2A-VDD_D18)") (class "Default")
      (node (ref "C19") (pin "1") (pinfunction "1_1") (pintype "passive"))
      (node (ref "IC2") (pin "23") (pinfunction "VDD_D18_23") (pintype "power_in"))
      (node (ref "L3") (pin "1") (pinfunction "1_1") (pintype "passive"))
    )
    (net (code "42") (name "Net-(IC2A-X1)") (class "Default")
      (node (ref "C29") (pin "1") (pinfunction "1_1") (pintype "passive"))
      (node (ref "IC2") (pin "20") (pinfunction "X1_20") (pintype "bidirectional"))
      (node (ref "Q2") (pin "1") (pinfunction "P$1_1") (pintype "passive"))
    )
    (net (code "43") (name "Net-(IC2A-X2)") (class "Default")
      (node (ref "C21") (pin "1") (pinfunction "1_1") (pintype "passive"))
      (node (ref "IC2") (pin "21") (pinfunction "X2_21") (pintype "bidirectional"))
      (node (ref "Q2") (pin "2") (pinfunction "P$2_2") (pintype "passive"))
    )
    (net (code "44") (name "Net-(IC2A-~{RST})") (class "Default")
      (node (ref "IC2") (pin "19") (pinfunction "~{RST}_19") (pintype "bidirectional"))
      (node (ref "T1") (pin "3") (pinfunction "D_3") (pintype "passive"))
    )
    (net (code "45") (name "Net-(IC3-AVCC)") (class "Default")
      (node (ref "C10") (pin "2") (pinfunction "2_2") (pintype "passive"))
      (node (ref "C17") (pin "2") (pinfunction "2_2") (pintype "passive"))
      (node (ref "C47") (pin "2") (pinfunction "2_2") (pintype "passive"))
      (node (ref "IC3") (pin "32") (pinfunction "AVCC_32") (pintype "power_in"))
      (node (ref "L4") (pin "2") (pinfunction "2_2") (pintype "passive"))
    )
    (net (code "46") (name "Net-(IC3-PR0-XTAL2_TOSC2_CLKOUT_EVOUT_RTCOUT_AC1OUT)") (class "Default")
      (node (ref "C32") (pin "1") (pinfunction "1_1") (pintype "passive"))
      (node (ref "IC3") (pin "20") (pinfunction "PR0-XTAL2_TOSC2_CLKOUT_EVOUT_RTCOUT_AC1OUT_20") (pintype "bidirectional"))
      (node (ref "Q1") (pin "2") (pinfunction "P$2_2") (pintype "passive"))
    )
    (net (code "47") (name "Net-(IC3-PR1-XTAL1_TOSC1_EXTCLK_AC0OUT)") (class "Default")
      (node (ref "C33") (pin "1") (pinfunction "1_1") (pintype "passive"))
      (node (ref "IC3") (pin "19") (pinfunction "PR1-XTAL1_TOSC1_EXTCLK_AC0OUT_19") (pintype "bidirectional"))
      (node (ref "Q1") (pin "1") (pinfunction "P$1_1") (pintype "passive"))
    )
    (net (code "48") (name "Net-(IC3-VCC)") (class "Default")
      (node (ref "C12") (pin "2") (pinfunction "2_2") (pintype "passive"))
      (node (ref "C20") (pin "2") (pinfunction "2_2") (pintype "passive"))
      (node (ref "IC3") (pin "17") (pinfunction "VCC_17") (pintype "power_in"))
      (node (ref "L9") (pin "2") (pinfunction "2_2") (pintype "passive"))
    )
    (net (code "49") (name "Net-(IC4--INF)") (class "Default")
      (node (ref "IC4") (pin "1") (pinfunction "-INS_1") (pintype "input"))
      (node (ref "IC4") (pin "2") (pinfunction "-INF_2") (pintype "input"))
      (node (ref "R19") (pin "2") (pinfunction "2_2") (pintype "passive"))
    )
    (net (code "50") (name "Net-(IC4-OUT)") (class "Default")
      (node (ref "IC4") (pin "4") (pinfunction "OUT_4") (pintype "open_collector"))
      (node (ref "R28") (pin "1") (pinfunction "1_1") (pintype "passive"))
      (node (ref "R29") (pin "1") (pinfunction "1_1") (pintype "passive"))
    )
    (net (code "51") (name "Net-(IC4-VREG)") (class "Default")
      (node (ref "C27") (pin "1") (pinfunction "1_1") (pintype "passive"))
      (node (ref "IC4") (pin "6") (pinfunction "VREG_6") (pintype "bidirectional"))
    )
    (net (code "52") (name "Net-(IC7-COMP)") (class "Default")
      (node (ref "C42") (pin "2") (pinfunction "2_2") (pintype "passive"))
      (node (ref "C43") (pin "1") (pinfunction "1_1") (pintype "passive"))
      (node (ref "IC7") (pin "4") (pinfunction "COMP_4") (pintype "bidirectional"))
    )
    (net (code "53") (name "Net-(IC7-CS+)") (class "Default")
      (node (ref "D19") (pin "A") (pinfunction "A_A") (pintype "passive"))
      (node (ref "IC7") (pin "2") (pinfunction "CS+_2") (pintype "input"))
      (node (ref "L6") (pin "2") (pinfunction "2_2") (pintype "passive"))
      (node (ref "R55") (pin "1") (pinfunction "1_1") (pintype "passive"))
    )
    (net (code "54") (name "Net-(IC7-FB)") (class "Default")
      (node (ref "IC7") (pin "5") (pinfunction "FB_5") (pintype "input"))
      (node (ref "R43") (pin "1") (pinfunction "1_1") (pintype "passive"))
      (node (ref "R47") (pin "2") (pinfunction "2_2") (pintype "passive"))
    )
    (net (code "55") (name "Net-(IC7-OUT)") (class "Default")
      (node (ref "D18") (pin "K") (pinfunction "K_K") (pintype "passive"))
      (node (ref "IC7") (pin "1") (pinfunction "OUT_1") (pintype "output"))
      (node (ref "L6") (pin "1") (pinfunction "1_1") (pintype "passive"))
    )
    (net (code "56") (name "Net-(IC7-VCC)") (class "Default")
      (node (ref "C44") (pin "2") (pinfunction "2_2") (pintype "passive"))
      (node (ref "C45") (pin "+") (pinfunction "+_+") (pintype "passive"))
      (node (ref "D19") (pin "K") (pinfunction "K_K") (pintype "passive"))
      (node (ref "IC7") (pin "8") (pinfunction "VCC_8") (pintype "power_in"))
      (node (ref "L12") (pin "2") (pinfunction "2_2") (pintype "passive"))
    )
    (net (code "57") (name "Net-(J6-GND)") (class "Default")
      (node (ref "C25") (pin "2") (pinfunction "2_2") (pintype "passive"))
      (node (ref "J6") (pin "P$8") (pinfunction "GND_P$8") (pintype "passive"))
    )
    (net (code "58") (name "Net-(J6-RCT)") (class "Default")
      (node (ref "C14") (pin "2") (pinfunction "2_2") (pintype "passive"))
      (node (ref "C18") (pin "2") (pinfunction "2_2") (pintype "passive"))
      (node (ref "J6") (pin "P$4") (pinfunction "TCT_P$4") (pintype "passive"))
      (node (ref "J6") (pin "P$5") (pinfunction "RCT_P$5") (pintype "passive"))
      (node (ref "L5") (pin "1") (pinfunction "1_1") (pintype "passive"))
    )
    (net (code "59") (name "Net-(R10-Pad1)") (class "Default")
      (node (ref "R10") (pin "1") (pinfunction "1_1") (pintype "passive"))
      (node (ref "R30") (pin "1") (pinfunction "1_1") (pintype "passive"))
      (node (ref "R9") (pin "2") (pinfunction "2_2") (pintype "passive"))
    )
    (net (code "60") (name "Net-(R10-Pad2)") (class "Default")
      (node (ref "R10") (pin "2") (pinfunction "2_2") (pintype "passive"))
      (node (ref "R14") (pin "1") (pinfunction "1_1") (pintype "passive"))
    )
    (net (code "61") (name "Net-(T2-D)") (class "Default")
      (node (ref "D8") (pin "A") (pinfunction "A_A") (pintype "passive"))
      (node (ref "J1") (pin "2") (pinfunction "2_2") (pintype "passive"))
      (node (ref "T2") (pin "2") (pinfunction "D_2") (pintype "passive"))
      (node (ref "T2") (pin "4") (pinfunction "D1_4") (pintype "passive"))
    )
    (net (code "62") (name "Net-(T2-G)") (class "Default")
      (node (ref "D3") (pin "K") (pinfunction "K_K") (pintype "passive"))
      (node (ref "R13") (pin "1") (pinfunction "1_1") (pintype "passive"))
      (node (ref "T2") (pin "1") (pinfunction "G_1") (pintype "passive"))
    )
    (net (code "63") (name "PDI_CLK") (class "Default")
      (node (ref "C13") (pin "1") (pinfunction "1_1") (pintype "passive"))
      (node (ref "IC3") (pin "8") (pinfunction "PDI_CLK/RESET_8") (pintype "bidirectional"))
      (node (ref "J5") (pin "6") (pinfunction "6_6") (pintype "passive"))
      (node (ref "R17") (pin "1") (pinfunction "1_1") (pintype "passive"))
    )
    (net (code "64") (name "PDI_DATA") (class "Default")
      (node (ref "IC3") (pin "7") (pinfunction "PDI_DATA_7") (pintype "bidirectional"))
      (node (ref "J5") (pin "2") (pinfunction "2_2") (pintype "passive"))
    )
    (net (code "65") (name "PE") (class "Default")
      (node (ref "C23") (pin "2") (pinfunction "2_2") (pintype "passive"))
      (node (ref "C25") (pin "1") (pinfunction "1_1") (pintype "passive"))
      (node (ref "J6") (pin "P$10") (pinfunction "10_P$10") (pintype "passive"))
      (node (ref "J6") (pin "P$9") (pinfunction "9_P$9") (pintype "passive"))
      (node (ref "R3") (pin "2") (pinfunction "2_2") (pintype "passive"))
    )
    (net (code "66") (name "RS485_A") (class "Default")
      (node (ref "D1") (pin "A") (pinfunction "1_A") (pintype "passive"))
      (node (ref "J2") (pin "3") (pinfunction "3_3") (pintype "passive"))
      (node (ref "L13") (pin "3") (pinfunction "4_3") (pintype "passive"))
      (node (ref "R34") (pin "1") (pinfunction "1_1") (pintype "passive"))
    )
    (net (code "67") (name "RS485_B") (class "Default")
      (node (ref "D4") (pin "A") (pinfunction "1_A") (pintype "passive"))
      (node (ref "J2") (pin "2") (pinfunction "2_2") (pintype "passive"))
      (node (ref "L13") (pin "1") (pinfunction "1_1") (pintype "passive"))
      (node (ref "R35") (pin "1") (pinfunction "1_1") (pintype "passive"))
    )
    (net (code "68") (name "RS485_ENA") (class "Default")
      (node (ref "IC1") (pin "2") (pinfunction "/RE_2") (pintype "bidirectional"))
      (node (ref "IC1") (pin "3") (pinfunction "DE_3") (pintype "bidirectional"))
      (node (ref "IC3") (pin "27") (pinfunction "PD1-ADC9_XCK0_SCL_IN2_27") (pintype "bidirectional"))
      (node (ref "R20") (pin "2") (pinfunction "2_2") (pintype "passive"))
    )
    (net (code "69") (name "RS485_RX") (class "Default")
      (node (ref "IC1") (pin "1") (pinfunction "R0_1") (pintype "output"))
      (node (ref "IC3") (pin "26") (pinfunction "PD2-ADC10_RXD0_IN0_OC0_26") (pintype "bidirectional"))
      (node (ref "R21") (pin "1") (pinfunction "1_1") (pintype "passive"))
    )
    (net (code "70") (name "RS485_TX") (class "Default")
      (node (ref "IC1") (pin "4") (pinfunction "DI_4") (pintype "input"))
      (node (ref "IC3") (pin "25") (pinfunction "PD3-ADC11_TXD0_IN3_OC1_25") (pintype "bidirectional"))
    )
    (net (code "71") (name "SCL{slash}RXD_EXT") (class "Default")
      (node (ref "IC3") (pin "15") (pinfunction "PC1-OC4B_OC4AHS_XCK0_SCL_IN2_15") (pintype "bidirectional"))
      (node (ref "R27") (pin "1") (pinfunction "1_1") (pintype "passive"))
    )
    (net (code "72") (name "SDA{slash}TXD_EXT") (class "Default")
      (node (ref "IC3") (pin "16") (pinfunction "PC0-OC4A_OC4ALS_SDA_IN1/OUT0_16") (pintype "bidirectional"))
      (node (ref "R24") (pin "1") (pinfunction "1_1") (pintype "passive"))
    )
    (net (code "73") (name "U_VIN") (class "Default")
      (node (ref "C26") (pin "2") (pinfunction "2_2") (pintype "passive"))
      (node (ref "IC3") (pin "6") (pinfunction "PA0-ADC0_AC0_AREF_6") (pintype "bidirectional"))
      (node (ref "R30") (pin "2") (pinfunction "2_2") (pintype "passive"))
    )
    (net (code "74") (name "V_LED") (class "Default")
      (node (ref "IC4") (pin "8") (pinfunction "+IN_8") (pintype "input"))
      (node (ref "J2") (pin "5") (pinfunction "5_5") (pintype "passive"))
      (node (ref "R18") (pin "1") (pinfunction "1_1") (pintype "passive"))
    )
    (net (code "75") (name "unconnected-(IC2A-EDD_IO-Pad6)") (class "Default")
      (node (ref "IC2") (pin "6") (pinfunction "EDD_IO_6") (pintype "bidirectional"))
    )
    (net (code "76") (name "unconnected-(IC2A-EECS-Pad10)") (class "Default")
      (node (ref "IC2") (pin "10") (pinfunction "EECS_10") (pintype "bidirectional"))
    )
    (net (code "77") (name "unconnected-(IC2A-EESK-Pad7)") (class "Default")
      (node (ref "IC2") (pin "7") (pinfunction "EESK_7") (pintype "bidirectional"))
    )
    (net (code "78") (name "unconnected-(IC2A-LED0-Pad1)") (class "Default")
      (node (ref "IC2") (pin "1") (pinfunction "LED0_1") (pintype "bidirectional"))
    )
    (net (code "79") (name "unconnected-(IC2A-LED1-Pad32)") (class "Default")
      (node (ref "IC2") (pin "32") (pinfunction "LED1_32") (pintype "bidirectional"))
    )
    (net (code "80") (name "unconnected-(IC3-PA2-ADC2_AC2-Pad4)") (class "Default")
      (node (ref "IC3") (pin "4") (pinfunction "PA2-ADC2_AC2_4") (pintype "bidirectional"))
    )
    (net (code "81") (name "unconnected-(IC3-PA3-ADC3_AC3-Pad3)") (class "Default")
      (node (ref "IC3") (pin "3") (pinfunction "PA3-ADC3_AC3_3") (pintype "bidirectional"))
    )
    (net (code "82") (name "unconnected-(IC3-PA4-ADC4_AC4-Pad2)") (class "Default")
      (node (ref "IC3") (pin "2") (pinfunction "PA4-ADC4_AC4_2") (pintype "bidirectional"))
    )
    (net (code "83") (name "unconnected-(IC3-PA5-ADC5_AC5-Pad31)") (class "Default")
      (node (ref "IC3") (pin "31") (pinfunction "PA5-ADC5_AC5_31") (pintype "bidirectional"))
    )
    (net (code "84") (name "unconnected-(IC3-PA6-ADC6_AC6_AC1OUT-Pad30)") (class "Default")
      (node (ref "IC3") (pin "30") (pinfunction "PA6-ADC6_AC6_AC1OUT_30") (pintype "bidirectional"))
    )
    (net (code "85") (name "unconnected-(IC3-PA7-ADC7_AC7_AC0OUT-Pad29)") (class "Default")
      (node (ref "IC3") (pin "29") (pinfunction "PA7-ADC7_AC7_AC0OUT_29") (pintype "bidirectional"))
    )
    (net (code "86") (name "unconnected-(IC3-PD0-ADC8_SDA_IN1{slash}OUT0_AREF-Pad28)") (class "Default")
      (node (ref "IC3") (pin "28") (pinfunction "PD0-ADC8_SDA_IN1/OUT0_AREF_28") (pintype "bidirectional"))
    )
    (net (code "87") (name "unconnected-(IC3-PD6-ADC14_RXD0_IN0_RTCOUT_AC1OUT-Pad22)") (class "Default")
      (node (ref "IC3") (pin "22") (pinfunction "PD6-ADC14_RXD0_IN0_RTCOUT_AC1OUT_22") (pintype "bidirectional"))
    )
    (net (code "88") (name "unconnected-(IC3-PD7-ADC15_TXD0_IN3_CLKOUT_EVOUT_AC0OUT-Pad21)") (class "Default")
      (node (ref "IC3") (pin "21") (pinfunction "PD7-ADC15_TXD0_IN3_CLKOUT_EVOUT_AC0OUT_21") (pintype "bidirectional"))
    )
    (net (code "89") (name "unconnected-(IC7-VREF-Pad6)") (class "Default")
      (node (ref "IC7") (pin "6") (pinfunction "VREF_6") (pintype "bidirectional"))
    )
    (net (code "90") (name "unconnected-(J5-Pad1)") (class "Default")
      (node (ref "J5") (pin "1") (pinfunction "1_1") (pintype "passive"))
    )
    (net (code "91") (name "unconnected-(J5-Pad3)") (class "Default")
      (node (ref "J5") (pin "3") (pinfunction "3_3") (pintype "passive"))
    )
    (net (code "92") (name "unconnected-(J6-NC-PadP$7)") (class "Default")
      (node (ref "J6") (pin "P$7") (pinfunction "NC_P$7") (pintype "passive"))
    )
  )
)
